# rca_studio_II_single_v3.net
KiCad netlist of a schematic drawn in EAGLE
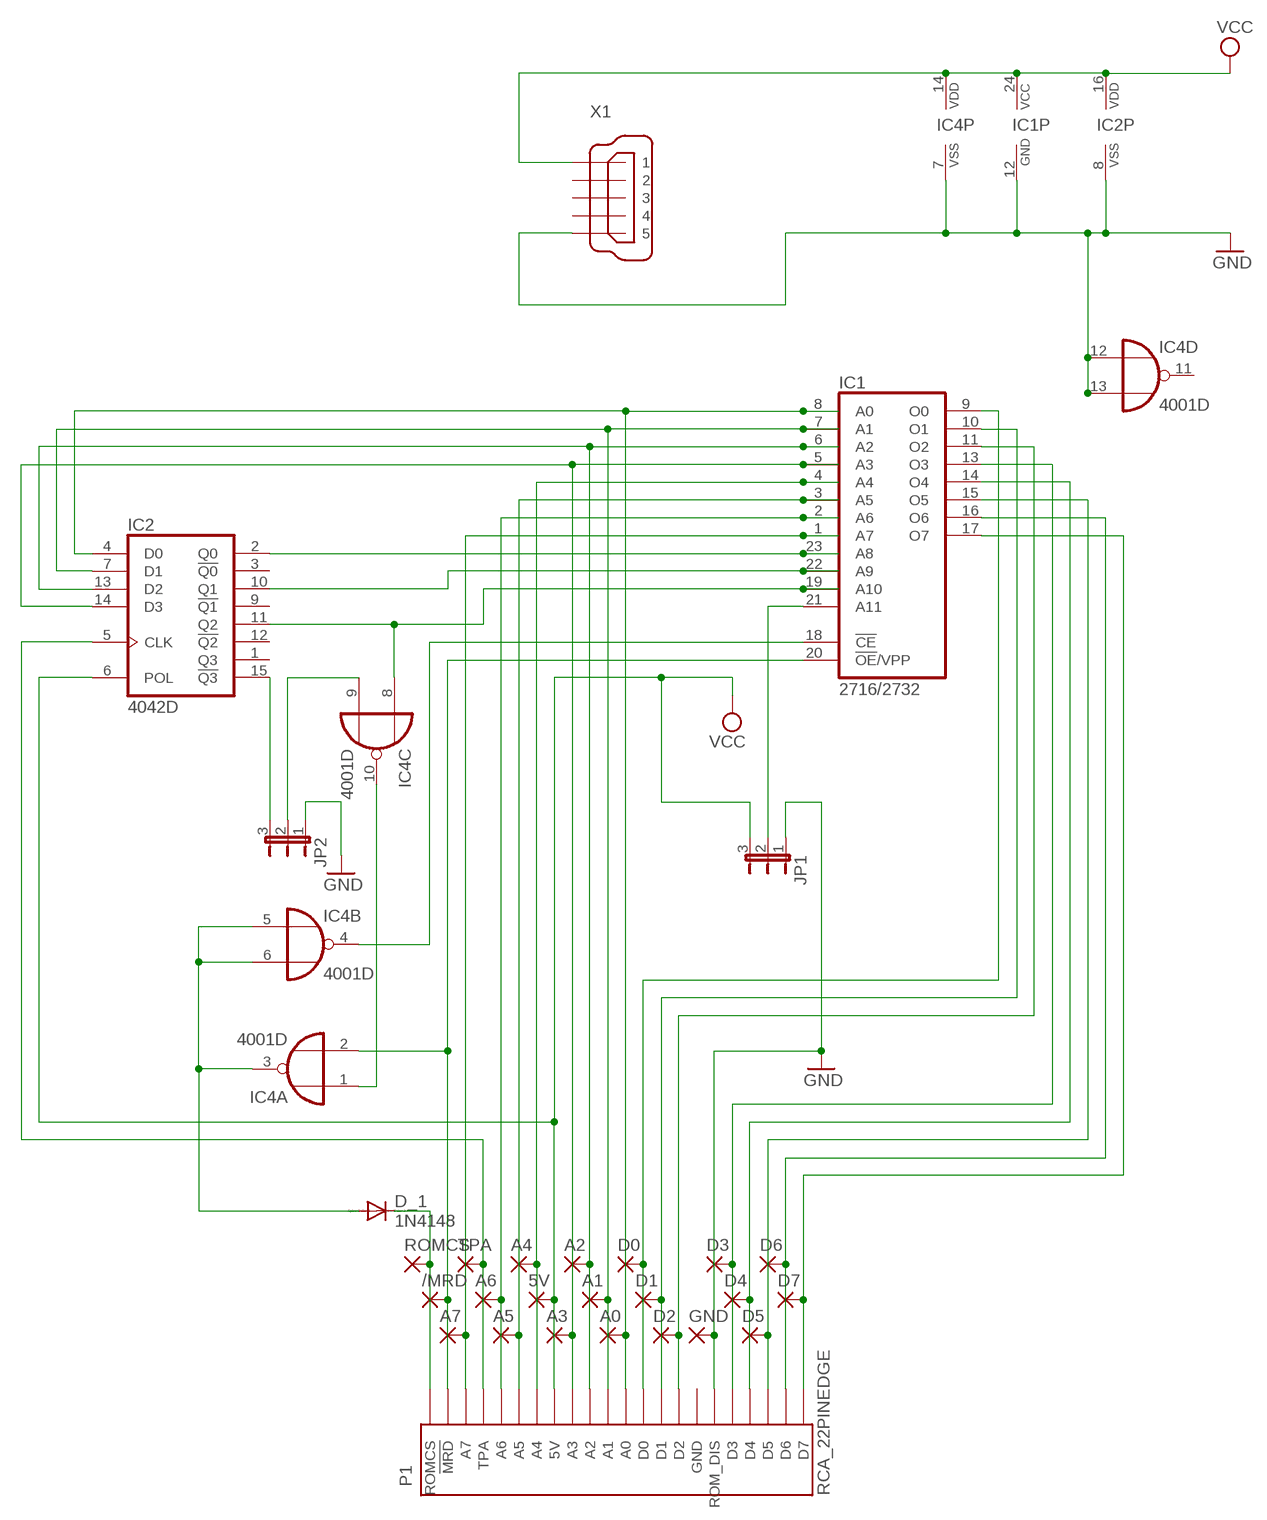
[diagram p0: schematic, sheet 1]

(export (version "E")
  (design (tool "Eeschema 10.0.6"))
  (components
    (comp (ref "/MRD")
      (value "WIREPAD2,15/1,0")
      (footprint "eagle-import:2,15_1,0")
      (libsource (lib "eagle-import") (part "WIREPAD2,15/1,0"))
    )
    (comp (ref "5V")
      (value "WIREPAD2,15/1,0")
      (footprint "eagle-import:2,15_1,0")
      (libsource (lib "eagle-import") (part "WIREPAD2,15/1,0"))
    )
    (comp (ref "A0")
      (value "WIREPAD2,15/1,0")
      (footprint "eagle-import:2,15_1,0")
      (libsource (lib "eagle-import") (part "WIREPAD2,15/1,0"))
    )
    (comp (ref "A1")
      (value "WIREPAD2,15/1,0")
      (footprint "eagle-import:2,15_1,0")
      (libsource (lib "eagle-import") (part "WIREPAD2,15/1,0"))
    )
    (comp (ref "A2")
      (value "WIREPAD2,15/1,0")
      (footprint "eagle-import:2,15_1,0")
      (libsource (lib "eagle-import") (part "WIREPAD2,15/1,0"))
    )
    (comp (ref "A3")
      (value "WIREPAD2,15/1,0")
      (footprint "eagle-import:2,15_1,0")
      (libsource (lib "eagle-import") (part "WIREPAD2,15/1,0"))
    )
    (comp (ref "A4")
      (value "WIREPAD2,15/1,0")
      (footprint "eagle-import:2,15_1,0")
      (libsource (lib "eagle-import") (part "WIREPAD2,15/1,0"))
    )
    (comp (ref "A5")
      (value "WIREPAD2,15/1,0")
      (footprint "eagle-import:2,15_1,0")
      (libsource (lib "eagle-import") (part "WIREPAD2,15/1,0"))
    )
    (comp (ref "A6")
      (value "WIREPAD2,15/1,0")
      (footprint "eagle-import:2,15_1,0")
      (libsource (lib "eagle-import") (part "WIREPAD2,15/1,0"))
    )
    (comp (ref "A7")
      (value "WIREPAD2,15/1,0")
      (footprint "eagle-import:2,15_1,0")
      (libsource (lib "eagle-import") (part "WIREPAD2,15/1,0"))
    )
    (comp (ref "D0")
      (value "WIREPAD2,15/1,0")
      (footprint "eagle-import:2,15_1,0")
      (libsource (lib "eagle-import") (part "WIREPAD2,15/1,0"))
    )
    (comp (ref "D1")
      (value "WIREPAD2,15/1,0")
      (footprint "eagle-import:2,15_1,0")
      (libsource (lib "eagle-import") (part "WIREPAD2,15/1,0"))
    )
    (comp (ref "D2")
      (value "WIREPAD2,15/1,0")
      (footprint "eagle-import:2,15_1,0")
      (libsource (lib "eagle-import") (part "WIREPAD2,15/1,0"))
    )
    (comp (ref "D3")
      (value "WIREPAD2,15/1,0")
      (footprint "eagle-import:2,15_1,0")
      (libsource (lib "eagle-import") (part "WIREPAD2,15/1,0"))
    )
    (comp (ref "D4")
      (value "WIREPAD2,15/1,0")
      (footprint "eagle-import:2,15_1,0")
      (libsource (lib "eagle-import") (part "WIREPAD2,15/1,0"))
    )
    (comp (ref "D5")
      (value "WIREPAD2,15/1,0")
      (footprint "eagle-import:2,15_1,0")
      (libsource (lib "eagle-import") (part "WIREPAD2,15/1,0"))
    )
    (comp (ref "D6")
      (value "WIREPAD2,15/1,0")
      (footprint "eagle-import:2,15_1,0")
      (libsource (lib "eagle-import") (part "WIREPAD2,15/1,0"))
    )
    (comp (ref "D7")
      (value "WIREPAD2,15/1,0")
      (footprint "eagle-import:2,15_1,0")
      (libsource (lib "eagle-import") (part "WIREPAD2,15/1,0"))
    )
    (comp (ref "D_1")
      (value "1N4148")
      (footprint "eagle-import:DO35-7")
      (libsource (lib "eagle-import") (part "1N4148DO35-7"))
    )
    (comp (ref "GND")
      (value "WIREPAD2,15/1,0")
      (footprint "eagle-import:2,15_1,0")
      (libsource (lib "eagle-import") (part "WIREPAD2,15/1,0"))
    )
    (comp (ref "IC1")
      (value "2716/2732")
      (footprint "eagle-import:DIL24")
      (libsource (lib "eagle-import") (part "2732"))
    )
    (comp (ref "IC2")
      (value "4042D")
      (footprint "eagle-import:SO16")
      (libsource (lib "eagle-import") (part "4042D"))
    )
    (comp (ref "IC4")
      (value "4001D")
      (footprint "eagle-import:SO14")
      (libsource (lib "eagle-import") (part "4001D"))
    )
    (comp (ref "JP1")
      (value "JP2E")
      (footprint "eagle-import:JP2")
      (libsource (lib "eagle-import") (part "JP2E"))
    )
    (comp (ref "JP2")
      (value "JP2E")
      (footprint "eagle-import:JP2")
      (libsource (lib "eagle-import") (part "JP2E"))
    )
    (comp (ref "P1")
      (value "RCA_22PINEDGE")
      (footprint "eagle-import:RCA_22PINEDGE")
      (libsource (lib "eagle-import") (part "RCA_22PINEDGE"))
    )
    (comp (ref "ROMCS")
      (value "WIREPAD2,15/1,0")
      (footprint "eagle-import:2,15_1,0")
      (libsource (lib "eagle-import") (part "WIREPAD2,15/1,0"))
    )
    (comp (ref "TPA")
      (value "WIREPAD2,15/1,0")
      (footprint "eagle-import:2,15_1,0")
      (libsource (lib "eagle-import") (part "WIREPAD2,15/1,0"))
    )
    (comp (ref "X1")
      (value "MINI-USB-32005-301")
      (footprint "eagle-import:32005-301")
      (libsource (lib "eagle-import") (part "MINI-USB-32005-301"))
    )
  )
  (nets
    (net (code "1") (name "GND") (class "Default")
      (node (ref "GND") (pin "1") (pinfunction "P_1") (pintype "passive"))
      (node (ref "IC1") (pin "12") (pinfunction "GND_12") (pintype "power_in"))
      (node (ref "IC2") (pin "8") (pinfunction "VSS_8") (pintype "power_in"))
      (node (ref "IC4") (pin "12") (pinfunction "I0_12") (pintype "input"))
      (node (ref "IC4") (pin "13") (pinfunction "I1_13") (pintype "input"))
      (node (ref "IC4") (pin "7") (pinfunction "VSS_7") (pintype "power_in"))
      (node (ref "JP1") (pin "1") (pinfunction "1_1") (pintype "passive"))
      (node (ref "JP2") (pin "1") (pinfunction "1_1") (pintype "passive"))
      (node (ref "P1") (pin "6") (pinfunction "ROM_DIS_6") (pintype "passive"))
      (node (ref "X1") (pin "5") (pinfunction "5_5") (pintype "passive"))
    )
    (net (code "2") (name "Net-(/MRD-P)") (class "Default")
      (node (ref "/MRD") (pin "1") (pinfunction "P_1") (pintype "passive"))
      (node (ref "IC1") (pin "20") (pinfunction "~{OE}/VPP_20") (pintype "input"))
      (node (ref "IC4") (pin "2") (pinfunction "I1_2") (pintype "input"))
      (node (ref "P1") (pin "21") (pinfunction "~{MRD}_21") (pintype "passive"))
    )
    (net (code "3") (name "Net-(A0-P)") (class "Default")
      (node (ref "A0") (pin "1") (pinfunction "P_1") (pintype "passive"))
      (node (ref "IC1") (pin "8") (pinfunction "A0_8") (pintype "input"))
      (node (ref "IC2") (pin "4") (pinfunction "D0_4") (pintype "input"))
      (node (ref "P1") (pin "11") (pinfunction "A0_11") (pintype "passive"))
    )
    (net (code "4") (name "Net-(A1-P)") (class "Default")
      (node (ref "A1") (pin "1") (pinfunction "P_1") (pintype "passive"))
      (node (ref "IC1") (pin "7") (pinfunction "A1_7") (pintype "input"))
      (node (ref "IC2") (pin "7") (pinfunction "D1_7") (pintype "input"))
      (node (ref "P1") (pin "12") (pinfunction "A1_12") (pintype "passive"))
    )
    (net (code "5") (name "Net-(A2-P)") (class "Default")
      (node (ref "A2") (pin "1") (pinfunction "P_1") (pintype "passive"))
      (node (ref "IC1") (pin "6") (pinfunction "A2_6") (pintype "input"))
      (node (ref "IC2") (pin "13") (pinfunction "D2_13") (pintype "input"))
      (node (ref "P1") (pin "13") (pinfunction "A2_13") (pintype "passive"))
    )
    (net (code "6") (name "Net-(A3-P)") (class "Default")
      (node (ref "A3") (pin "1") (pinfunction "P_1") (pintype "passive"))
      (node (ref "IC1") (pin "5") (pinfunction "A3_5") (pintype "input"))
      (node (ref "IC2") (pin "14") (pinfunction "D3_14") (pintype "input"))
      (node (ref "P1") (pin "14") (pinfunction "A3_14") (pintype "passive"))
    )
    (net (code "7") (name "Net-(A4-P)") (class "Default")
      (node (ref "A4") (pin "1") (pinfunction "P_1") (pintype "passive"))
      (node (ref "IC1") (pin "4") (pinfunction "A4_4") (pintype "input"))
      (node (ref "P1") (pin "16") (pinfunction "A4_16") (pintype "passive"))
    )
    (net (code "8") (name "Net-(A5-P)") (class "Default")
      (node (ref "A5") (pin "1") (pinfunction "P_1") (pintype "passive"))
      (node (ref "IC1") (pin "3") (pinfunction "A5_3") (pintype "input"))
      (node (ref "P1") (pin "17") (pinfunction "A5_17") (pintype "passive"))
    )
    (net (code "9") (name "Net-(A6-P)") (class "Default")
      (node (ref "A6") (pin "1") (pinfunction "P_1") (pintype "passive"))
      (node (ref "IC1") (pin "2") (pinfunction "A6_2") (pintype "input"))
      (node (ref "P1") (pin "18") (pinfunction "A6_18") (pintype "passive"))
    )
    (net (code "10") (name "Net-(A7-P)") (class "Default")
      (node (ref "A7") (pin "1") (pinfunction "P_1") (pintype "passive"))
      (node (ref "IC1") (pin "1") (pinfunction "A7_1") (pintype "input"))
      (node (ref "P1") (pin "20") (pinfunction "A7_20") (pintype "passive"))
    )
    (net (code "11") (name "Net-(D0-P)") (class "Default")
      (node (ref "D0") (pin "1") (pinfunction "P_1") (pintype "passive"))
      (node (ref "IC1") (pin "9") (pinfunction "O0_9") (pintype "tri_state"))
      (node (ref "P1") (pin "10") (pinfunction "D0_10") (pintype "passive"))
    )
    (net (code "12") (name "Net-(D1-P)") (class "Default")
      (node (ref "D1") (pin "1") (pinfunction "P_1") (pintype "passive"))
      (node (ref "IC1") (pin "10") (pinfunction "O1_10") (pintype "tri_state"))
      (node (ref "P1") (pin "9") (pinfunction "D1_9") (pintype "passive"))
    )
    (net (code "13") (name "Net-(D2-P)") (class "Default")
      (node (ref "D2") (pin "1") (pinfunction "P_1") (pintype "passive"))
      (node (ref "IC1") (pin "11") (pinfunction "O2_11") (pintype "tri_state"))
      (node (ref "P1") (pin "8") (pinfunction "D2_8") (pintype "passive"))
    )
    (net (code "14") (name "Net-(D3-P)") (class "Default")
      (node (ref "D3") (pin "1") (pinfunction "P_1") (pintype "passive"))
      (node (ref "IC1") (pin "13") (pinfunction "O3_13") (pintype "tri_state"))
      (node (ref "P1") (pin "5") (pinfunction "D3_5") (pintype "passive"))
    )
    (net (code "15") (name "Net-(D4-P)") (class "Default")
      (node (ref "D4") (pin "1") (pinfunction "P_1") (pintype "passive"))
      (node (ref "IC1") (pin "14") (pinfunction "O4_14") (pintype "tri_state"))
      (node (ref "P1") (pin "4") (pinfunction "D4_4") (pintype "passive"))
    )
    (net (code "16") (name "Net-(D5-P)") (class "Default")
      (node (ref "D5") (pin "1") (pinfunction "P_1") (pintype "passive"))
      (node (ref "IC1") (pin "15") (pinfunction "O5_15") (pintype "tri_state"))
      (node (ref "P1") (pin "3") (pinfunction "D5_3") (pintype "passive"))
    )
    (net (code "17") (name "Net-(D6-P)") (class "Default")
      (node (ref "D6") (pin "1") (pinfunction "P_1") (pintype "passive"))
      (node (ref "IC1") (pin "16") (pinfunction "O6_16") (pintype "tri_state"))
      (node (ref "P1") (pin "2") (pinfunction "D6_2") (pintype "passive"))
    )
    (net (code "18") (name "Net-(D7-P)") (class "Default")
      (node (ref "D7") (pin "1") (pinfunction "P_1") (pintype "passive"))
      (node (ref "IC1") (pin "17") (pinfunction "O7_17") (pintype "tri_state"))
      (node (ref "P1") (pin "1") (pinfunction "D7_1") (pintype "passive"))
    )
    (net (code "19") (name "Net-(IC1A-A8)") (class "Default")
      (node (ref "IC1") (pin "23") (pinfunction "A8_23") (pintype "input"))
      (node (ref "IC2") (pin "2") (pinfunction "Q0_2") (pintype "output"))
    )
    (net (code "20") (name "Net-(IC1A-A9)") (class "Default")
      (node (ref "IC1") (pin "22") (pinfunction "A9_22") (pintype "input"))
      (node (ref "IC2") (pin "10") (pinfunction "Q1_10") (pintype "output"))
    )
    (net (code "21") (name "Net-(IC1A-A10)") (class "Default")
      (node (ref "IC1") (pin "19") (pinfunction "A10_19") (pintype "input"))
      (node (ref "IC2") (pin "11") (pinfunction "Q2_11") (pintype "output"))
      (node (ref "IC4") (pin "8") (pinfunction "I0_8") (pintype "input"))
    )
    (net (code "22") (name "Net-(IC1A-A11)") (class "Default")
      (node (ref "IC1") (pin "21") (pinfunction "A11_21") (pintype "input"))
      (node (ref "JP1") (pin "2") (pinfunction "2_2") (pintype "passive"))
    )
    (net (code "23") (name "Net-(IC1A-~{CE})") (class "Default")
      (node (ref "IC1") (pin "18") (pinfunction "~{CE}_18") (pintype "input"))
      (node (ref "IC4") (pin "4") (pinfunction "O_4") (pintype "output"))
    )
    (net (code "24") (name "Net-(IC2A-CLK)") (class "Default")
      (node (ref "IC2") (pin "5") (pinfunction "CLK_5") (pintype "input"))
      (node (ref "P1") (pin "19") (pinfunction "TPA_19") (pintype "passive"))
      (node (ref "TPA") (pin "1") (pinfunction "P_1") (pintype "passive"))
    )
    (net (code "25") (name "Net-(IC2A-~{Q3})") (class "Default")
      (node (ref "IC2") (pin "15") (pinfunction "~{Q3}_15") (pintype "output"))
      (node (ref "JP2") (pin "3") (pinfunction "3_3") (pintype "passive"))
    )
    (net (code "26") (name "Net-(IC4A-I0)") (class "Default")
      (node (ref "IC4") (pin "1") (pinfunction "I0_1") (pintype "input"))
      (node (ref "IC4") (pin "10") (pinfunction "O_10") (pintype "output"))
    )
    (net (code "27") (name "Net-(IC4A-O)") (class "Default")
      (node (ref "D_1") (pin "A") (pinfunction "A_A") (pintype "passive"))
      (node (ref "IC4") (pin "3") (pinfunction "O_3") (pintype "output"))
      (node (ref "IC4") (pin "5") (pinfunction "I0_5") (pintype "input"))
      (node (ref "IC4") (pin "6") (pinfunction "I1_6") (pintype "input"))
    )
    (net (code "28") (name "Net-(IC4C-I1)") (class "Default")
      (node (ref "IC4") (pin "9") (pinfunction "I1_9") (pintype "input"))
      (node (ref "JP2") (pin "2") (pinfunction "2_2") (pintype "passive"))
    )
    (net (code "29") (name "Net-(P1-ROMCS)") (class "Default")
      (node (ref "D_1") (pin "C") (pinfunction "C_C") (pintype "passive"))
      (node (ref "P1") (pin "22") (pinfunction "ROMCS_22") (pintype "passive"))
      (node (ref "ROMCS") (pin "1") (pinfunction "P_1") (pintype "passive"))
    )
    (net (code "30") (name "VCC") (class "Default")
      (node (ref "5V") (pin "1") (pinfunction "P_1") (pintype "passive"))
      (node (ref "IC1") (pin "24") (pinfunction "VCC_24") (pintype "power_in"))
      (node (ref "IC2") (pin "16") (pinfunction "VDD_16") (pintype "power_in"))
      (node (ref "IC2") (pin "6") (pinfunction "POL_6") (pintype "input"))
      (node (ref "IC4") (pin "14") (pinfunction "VDD_14") (pintype "power_in"))
      (node (ref "JP1") (pin "3") (pinfunction "3_3") (pintype "passive"))
      (node (ref "P1") (pin "15") (pinfunction "5V_15") (pintype "passive"))
      (node (ref "X1") (pin "1") (pinfunction "1_1") (pintype "passive"))
    )
    (net (code "31") (name "unconnected-(IC2A-Q3-Pad1)") (class "Default")
      (node (ref "IC2") (pin "1") (pinfunction "Q3_1") (pintype "output"))
    )
    (net (code "32") (name "unconnected-(IC2A-~{Q0}-Pad3)") (class "Default")
      (node (ref "IC2") (pin "3") (pinfunction "~{Q0}_3") (pintype "output"))
    )
    (net (code "33") (name "unconnected-(IC2A-~{Q1}-Pad9)") (class "Default")
      (node (ref "IC2") (pin "9") (pinfunction "~{Q1}_9") (pintype "output"))
    )
    (net (code "34") (name "unconnected-(IC2A-~{Q2}-Pad12)") (class "Default")
      (node (ref "IC2") (pin "12") (pinfunction "~{Q2}_12") (pintype "output"))
    )
    (net (code "35") (name "unconnected-(IC4D-O-Pad11)") (class "Default")
      (node (ref "IC4") (pin "11") (pinfunction "O_11") (pintype "output"))
    )
    (net (code "36") (name "unconnected-(P1-GND-Pad7)") (class "Default")
      (node (ref "P1") (pin "7") (pinfunction "GND_7") (pintype "passive"))
    )
    (net (code "37") (name "unconnected-(X1-Pad2)") (class "Default")
      (node (ref "X1") (pin "2") (pinfunction "2_2") (pintype "passive"))
    )
    (net (code "38") (name "unconnected-(X1-Pad3)") (class "Default")
      (node (ref "X1") (pin "3") (pinfunction "3_3") (pintype "passive"))
    )
    (net (code "39") (name "unconnected-(X1-Pad4)") (class "Default")
      (node (ref "X1") (pin "4") (pinfunction "4_4") (pintype "passive"))
    )
  )
)
